# ESQUEMATIC.net
KiCad netlist of a schematic drawn in EAGLE
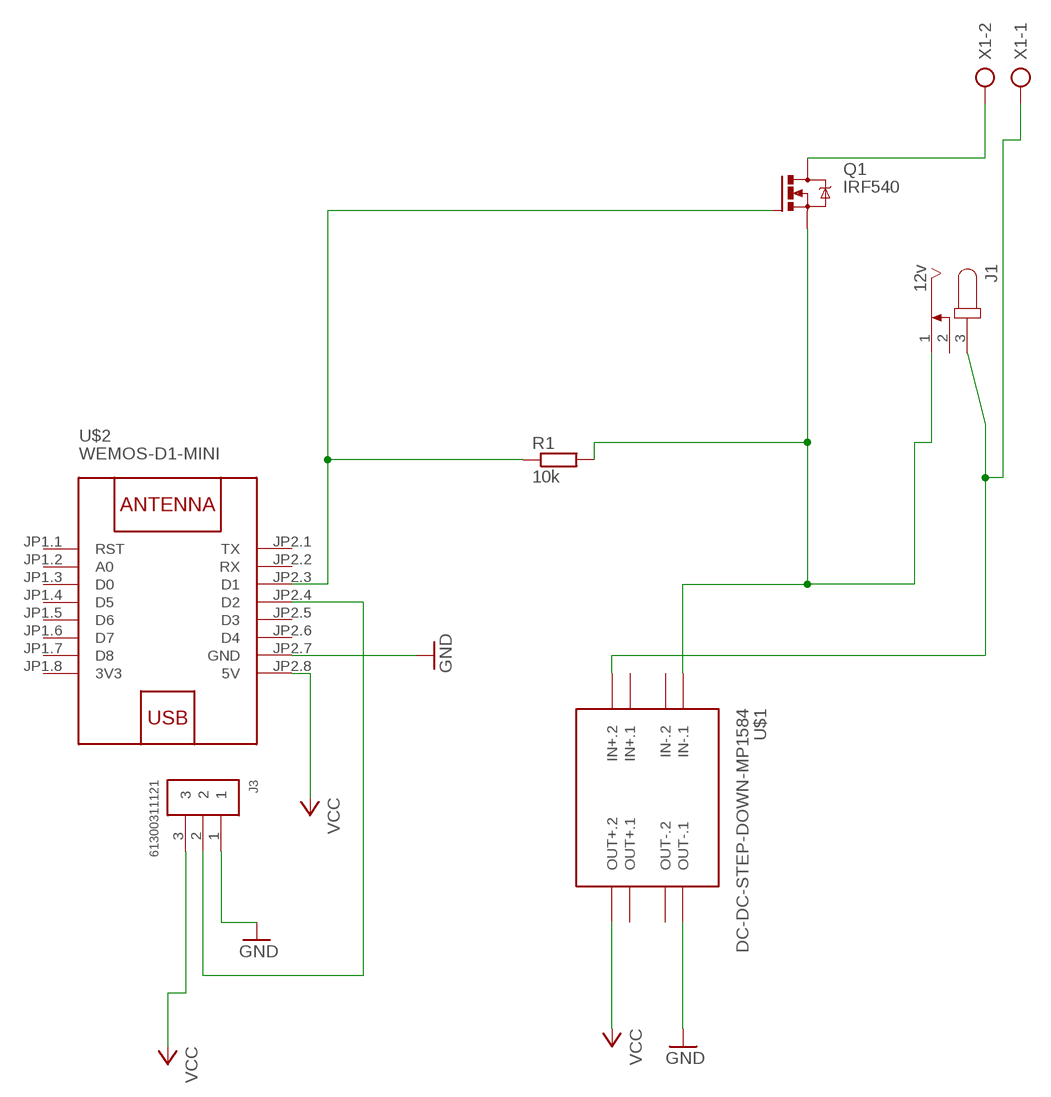
[diagram p0: schematic, sheet 1]

(export (version "E")
  (design (tool "Eeschema 10.0.6"))
  (components
    (comp (ref "J1")
      (value "12v")
      (footprint "eagle-import:SPC4077")
      (libsource (lib "eagle-import") (part "JACK-PLUG0"))
    )
    (comp (ref "J3")
      (value "61300311121")
      (footprint "eagle-import:61300311121")
      (fields
        (field (name "DIGI_KEY_PART_NUMBER") "732-5316-ND")
        (field (name "MANUFACTURER") "Wurth Electronics Inc.")
        (field (name "CREATED_BY") "PCBLayout.com")
      )
      (libsource (lib "eagle-import") (part "61300311121"))
    )
    (comp (ref "Q1")
      (value "IRF540")
      (footprint "eagle-import:TO220BV")
      (libsource (lib "eagle-import") (part "IRF540"))
    )
    (comp (ref "R1")
      (value "10k")
      (footprint "eagle-import:0204_7")
      (libsource (lib "eagle-import") (part "R-EU_0204/7"))
    )
    (comp (ref "U$1")
      (value "DC-DC-STEP-DOWN-MP1584")
      (footprint "eagle-import:DC-DC-STEP-DOWN-MP1584")
      (libsource (lib "eagle-import") (part "DC-DC-STEP-DOWN-MP1584"))
    )
    (comp (ref "U$2")
      (value "WEMOS-D1-MINI")
      (footprint "eagle-import:WEMOS-D1-MINI")
      (libsource (lib "eagle-import") (part "WEMOS-D1-MINI"))
    )
    (comp (ref "X1")
      (value "AK300/2")
      (footprint "eagle-import:AK300_2")
      (libsource (lib "eagle-import") (part "AK300/2"))
    )
  )
  (nets
    (net (code "1") (name "/3V3") (class "Default")
      (node (ref "U$2") (pin "JP1.8") (pinfunction "3V3_JP1.8") (pintype "power_in"))
    )
    (net (code "2") (name "GND") (class "Default")
      (node (ref "J3") (pin "1") (pinfunction "1_1") (pintype "passive"))
      (node (ref "U$1") (pin "OUT-.1") (pinfunction "OUT-.1_OUT-.1") (pintype "bidirectional"))
      (node (ref "U$2") (pin "JP2.7") (pinfunction "GND_JP2.7") (pintype "power_in"))
    )
    (net (code "3") (name "Net-(J1-Pad1)") (class "Default")
      (node (ref "J1") (pin "1") (pinfunction "1_1") (pintype "passive"))
      (node (ref "Q1") (pin "S") (pinfunction "S_S") (pintype "passive"))
      (node (ref "R1") (pin "2") (pinfunction "2_2") (pintype "passive"))
      (node (ref "U$1") (pin "IN-.1") (pinfunction "IN-.1_IN-.1") (pintype "bidirectional"))
    )
    (net (code "4") (name "Net-(U$2-D1)") (class "Default")
      (node (ref "Q1") (pin "G") (pinfunction "G_G") (pintype "passive"))
      (node (ref "R1") (pin "1") (pinfunction "1_1") (pintype "passive"))
      (node (ref "U$2") (pin "JP2.3") (pinfunction "D1_JP2.3") (pintype "bidirectional"))
    )
    (net (code "5") (name "Net-(U$2-D2)") (class "Default")
      (node (ref "J3") (pin "2") (pinfunction "2_2") (pintype "passive"))
      (node (ref "U$2") (pin "JP2.4") (pinfunction "D2_JP2.4") (pintype "bidirectional"))
    )
    (net (code "6") (name "Net-(X1A-KL)") (class "Default")
      (node (ref "J1") (pin "3") (pinfunction "3_3") (pintype "passive"))
      (node (ref "U$1") (pin "IN+.2") (pinfunction "IN+.2_IN+.2") (pintype "bidirectional"))
      (node (ref "X1") (pin "1") (pinfunction "KL_1") (pintype "passive"))
    )
    (net (code "7") (name "Net-(X1B-KL)") (class "Default")
      (node (ref "Q1") (pin "D") (pinfunction "D_D") (pintype "passive"))
      (node (ref "X1") (pin "2") (pinfunction "KL_2") (pintype "passive"))
    )
    (net (code "8") (name "VCC") (class "Default")
      (node (ref "J3") (pin "3") (pinfunction "3_3") (pintype "passive"))
      (node (ref "U$1") (pin "OUT+.2") (pinfunction "OUT+.2_OUT+.2") (pintype "bidirectional"))
      (node (ref "U$2") (pin "JP2.8") (pinfunction "5V_JP2.8") (pintype "power_in"))
    )
    (net (code "9") (name "unconnected-(J1-Pad2)") (class "Default")
      (node (ref "J1") (pin "2") (pinfunction "2_2") (pintype "passive"))
    )
    (net (code "10") (name "unconnected-(U$1-PadIN+.1)") (class "Default")
      (node (ref "U$1") (pin "IN+.1") (pinfunction "IN+.1_IN+.1") (pintype "bidirectional"))
    )
    (net (code "11") (name "unconnected-(U$1-PadIN-.2)") (class "Default")
      (node (ref "U$1") (pin "IN-.2") (pinfunction "IN-.2_IN-.2") (pintype "bidirectional"))
    )
    (net (code "12") (name "unconnected-(U$1-PadOUT+.1)") (class "Default")
      (node (ref "U$1") (pin "OUT+.1") (pinfunction "OUT+.1_OUT+.1") (pintype "bidirectional"))
    )
    (net (code "13") (name "unconnected-(U$1-PadOUT-.2)") (class "Default")
      (node (ref "U$1") (pin "OUT-.2") (pinfunction "OUT-.2_OUT-.2") (pintype "bidirectional"))
    )
    (net (code "14") (name "unconnected-(U$2-A0-PadJP1.2)") (class "Default")
      (node (ref "U$2") (pin "JP1.2") (pinfunction "A0_JP1.2") (pintype "bidirectional"))
    )
    (net (code "15") (name "unconnected-(U$2-D0-PadJP1.3)") (class "Default")
      (node (ref "U$2") (pin "JP1.3") (pinfunction "D0_JP1.3") (pintype "bidirectional"))
    )
    (net (code "16") (name "unconnected-(U$2-D3-PadJP2.5)") (class "Default")
      (node (ref "U$2") (pin "JP2.5") (pinfunction "D3_JP2.5") (pintype "bidirectional"))
    )
    (net (code "17") (name "unconnected-(U$2-D4-PadJP2.6)") (class "Default")
      (node (ref "U$2") (pin "JP2.6") (pinfunction "D4_JP2.6") (pintype "bidirectional"))
    )
    (net (code "18") (name "unconnected-(U$2-D5-PadJP1.4)") (class "Default")
      (node (ref "U$2") (pin "JP1.4") (pinfunction "D5_JP1.4") (pintype "bidirectional"))
    )
    (net (code "19") (name "unconnected-(U$2-D6-PadJP1.5)") (class "Default")
      (node (ref "U$2") (pin "JP1.5") (pinfunction "D6_JP1.5") (pintype "bidirectional"))
    )
    (net (code "20") (name "unconnected-(U$2-D7-PadJP1.6)") (class "Default")
      (node (ref "U$2") (pin "JP1.6") (pinfunction "D7_JP1.6") (pintype "bidirectional"))
    )
    (net (code "21") (name "unconnected-(U$2-D8-PadJP1.7)") (class "Default")
      (node (ref "U$2") (pin "JP1.7") (pinfunction "D8_JP1.7") (pintype "bidirectional"))
    )
    (net (code "22") (name "unconnected-(U$2-RST-PadJP1.1)") (class "Default")
      (node (ref "U$2") (pin "JP1.1") (pinfunction "RST_JP1.1") (pintype "bidirectional"))
    )
    (net (code "23") (name "unconnected-(U$2-RX-PadJP2.2)") (class "Default")
      (node (ref "U$2") (pin "JP2.2") (pinfunction "RX_JP2.2") (pintype "bidirectional"))
    )
    (net (code "24") (name "unconnected-(U$2-TX-PadJP2.1)") (class "Default")
      (node (ref "U$2") (pin "JP2.1") (pinfunction "TX_JP2.1") (pintype "bidirectional"))
    )
  )
)
